# LGT_Mini_Box.net
KiCad netlist of a schematic drawn in Altium Designer
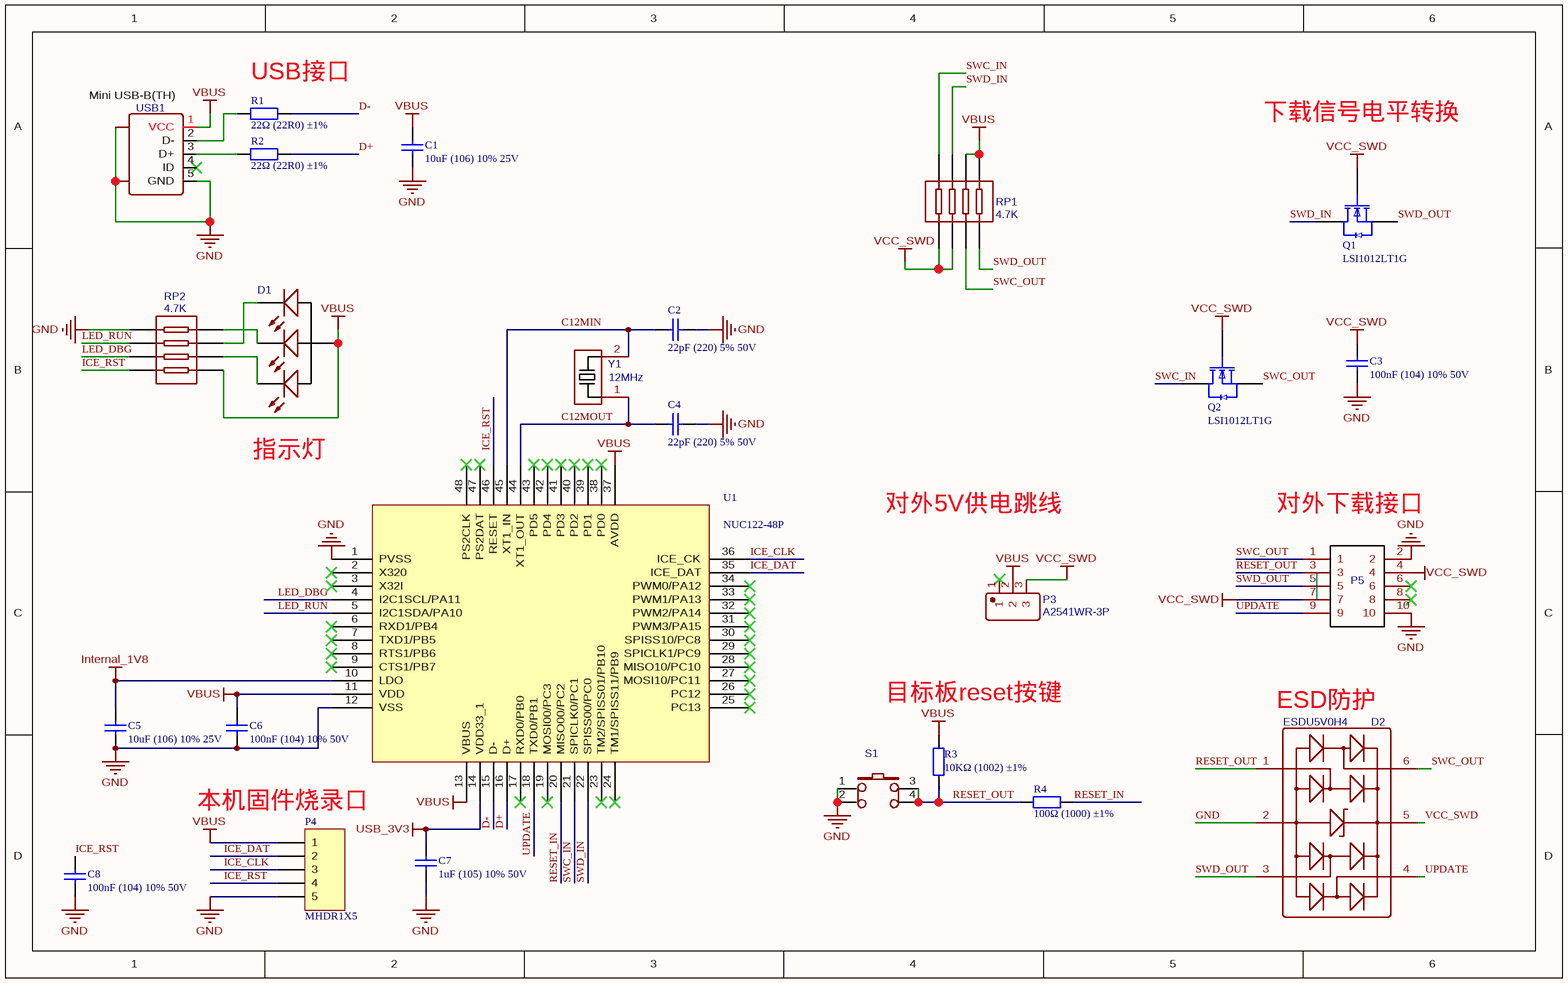
[diagram p0: LGT Mini Box.schdoc]

(export (version "E")
  (design (tool "Eeschema 10.0.6"))
  (components
    (comp (ref "C1")
      (value "10uF (106) 10% 25V")
      (libsource (lib "altium-import") (part "root_1_10uF (106) 10% 25V_"))
    )
    (comp (ref "C2")
      (value "22pF (220) 5% 50V")
      (libsource (lib "altium-import") (part "root_0_22pF (220) 5% 50V_"))
    )
    (comp (ref "C3")
      (value "100nF (104) 10% 50V")
      (libsource (lib "altium-import") (part "root_1_100nF (104) 10% 50V_"))
    )
    (comp (ref "C4")
      (value "22pF (220) 5% 50V")
      (libsource (lib "altium-import") (part "root_0_22pF (220) 5% 50V_"))
    )
    (comp (ref "C5")
      (value "10uF (106) 10% 25V")
      (libsource (lib "altium-import") (part "root_1_10uF (106) 10% 25V_"))
    )
    (comp (ref "C6")
      (value "100nF (104) 10% 50V")
      (libsource (lib "altium-import") (part "root_1_100nF (104) 10% 50V_"))
    )
    (comp (ref "C7")
      (value "1uF (105) 10% 50V")
      (libsource (lib "altium-import") (part "root_1_1uF (105) 10% 50V_"))
    )
    (comp (ref "C8")
      (value "100nF (104) 10% 50V")
      (libsource (lib "altium-import") (part "root_1_100nF (104) 10% 50V_"))
    )
    (comp (ref "D1")
      (value "FM-B2020RGBA-HG")
      (fields (field (name "BOM_SUPPLIER PART") "C108793") (field (name "CONTRIBUTOR") "LCSC"))
      (libsource (lib "altium-import") (part "root_2_FM-B2020RGBA-HG_"))
    )
    (comp (ref "D2")
      (value "ESDU5V0H4")
      (fields (field (name "BOM_SUPPLIER PART") "C84837"))
      (libsource (lib "altium-import") (part "root_3_ESDU5V0H4_"))
    )
    (comp (ref "P3")
      (value "A2541WR-3P")
      (fields (field (name "BOM_SUPPLIER PART") "C225489") (field (name "CONTRIBUTOR") "LCSC"))
      (libsource (lib "altium-import") (part "root_2_A2541WR-3P_"))
    )
    (comp (ref "P4")
      (value "MHDR1X5")
      (fields (field (name "PUBLISHER") "Altium Limited"))
      (libsource (lib "altium-import") (part "root_0_MHDR1X5_"))
    )
    (comp (ref "P5")
      (value "LGT-Link-2.54-2X5P")
      (fields
        (field (name "BOM_MANUFACTURER PART") "IDC Box 2.54mm 2X5P")
        (field (name "BOM_SUPPLIER PART") "C5665")
      )
      (libsource (lib "altium-import") (part "root_0_LGT-Link-2.54-2X5P_"))
    )
    (comp (ref "Q1") (value "LSI1012LT1G") (libsource (lib "altium-import") (part "root_3_LSI1012LT1G_")))
    (comp (ref "Q2") (value "LSI1012LT1G") (libsource (lib "altium-import") (part "root_3_LSI1012LT1G_")))
    (comp (ref "R1")
      (value "22Ω (22R0) ±1%")
      (libsource (lib "altium-import") (part "root_0_22Ω (22R0) ±1%_"))
    )
    (comp (ref "R2")
      (value "22Ω (22R0) ±1%")
      (libsource (lib "altium-import") (part "root_0_22Ω (22R0) ±1%_"))
    )
    (comp (ref "R3")
      (value "10KΩ (1002) ±1%")
      (libsource (lib "altium-import") (part "root_1_10KΩ (1002) ±1%_"))
    )
    (comp (ref "R4")
      (value "100Ω (1000) ±1%")
      (libsource (lib "altium-import") (part "root_2_100Ω (1000) ±1%_"))
    )
    (comp (ref "RP1")
      (value "4.7K")
      (fields
        (field (name "BOM_MANUFACTURER PART") "4D03WGJ0472T5E")
        (field (name "BOM_SUPPLIER PART") "C1980")
      )
      (libsource (lib "altium-import") (part "root_1_4.7K_"))
    )
    (comp (ref "RP2")
      (value "4.7K")
      (fields
        (field (name "BOM_MANUFACTURER PART") "4D03WGJ0472T5E")
        (field (name "BOM_SUPPLIER PART") "C1980")
      )
      (libsource (lib "altium-import") (part "root_0_4.7K_"))
    )
    (comp (ref "S1")
      (value "K2-1109DP-I4SW-01")
      (fields (field (name "BOM_SUPPLIER PART") "C223802") (field (name "CONTRIBUTOR") "LCSC"))
      (libsource (lib "altium-import") (part "root_0_K2-1109DP-I4SW-01_"))
    )
    (comp (ref "U1") (value "NUC122-48P") (libsource (lib "altium-import") (part "root_0_NUC122-48P_")))
    (comp (ref "USB1")
      (value "Mini USB-B 5P-Female-TH_C46398")
      (fields
        (field (name "BOM_MANUFACTURER PART") "MINI 5PFemale90Degree plate four feet copper shell LCPVinyl")
        (field (name "BOM_SUPPLIER PART") "C46398")
      )
      (libsource (lib "altium-import") (part "root_0_Mini USB-B 5P-Female-TH_C46398_"))
    )
    (comp (ref "Y1")
      (value "12MHz")
      (fields
        (field (name "BOM_MANUFACTURER PART") "CSTCE16M0V53C-R0")
        (field (name "BOM_SUPPLIER PART") "C91584")
        (field (name "CONTRIBUTOR") "costar")
      )
      (libsource (lib "altium-import") (part "root_1_12MHz_"))
    )
  )
  (nets
    (net (code "1") (name "/C12MIN") (class "Default")
      (node (ref "C2") (pin "1") (pinfunction "1_1") (pintype "passive"))
      (node (ref "U1") (pin "45") (pinfunction "XT1_IN_45") (pintype "passive"))
      (node (ref "Y1") (pin "2") (pinfunction "2_2") (pintype "passive"))
    )
    (net (code "2") (name "/C12MOUT") (class "Default")
      (node (ref "C4") (pin "1") (pinfunction "1_1") (pintype "passive"))
      (node (ref "U1") (pin "44") (pinfunction "XT1_OUT_44") (pintype "passive"))
      (node (ref "Y1") (pin "1") (pinfunction "1_1") (pintype "passive"))
    )
    (net (code "3") (name "/D+") (class "Default")
      (node (ref "R2") (pin "2") (pinfunction "2_2") (pintype "passive"))
      (node (ref "U1") (pin "16") (pinfunction "D+_16") (pintype "passive"))
    )
    (net (code "4") (name "/D-") (class "Default")
      (node (ref "R1") (pin "2") (pinfunction "2_2") (pintype "passive"))
      (node (ref "U1") (pin "15") (pinfunction "D-_15") (pintype "passive"))
    )
    (net (code "5") (name "/ICE_CLK") (class "Default")
      (node (ref "P4") (pin "3") (pinfunction "3_3") (pintype "passive"))
      (node (ref "U1") (pin "36") (pinfunction "ICE_CK_36") (pintype "passive"))
    )
    (net (code "6") (name "/ICE_DAT") (class "Default")
      (node (ref "P4") (pin "2") (pinfunction "2_2") (pintype "passive"))
      (node (ref "U1") (pin "35") (pinfunction "ICE_DAT_35") (pintype "passive"))
    )
    (net (code "7") (name "/ICE_RST") (class "Default")
      (node (ref "C8") (pin "2") (pinfunction "2_2") (pintype "passive"))
      (node (ref "P4") (pin "4") (pinfunction "4_4") (pintype "passive"))
      (node (ref "RP2") (pin "4") (pinfunction "4_4") (pintype "passive"))
      (node (ref "U1") (pin "46") (pinfunction "RESET_46") (pintype "passive"))
    )
    (net (code "8") (name "/LED_DBG") (class "Default")
      (node (ref "RP2") (pin "3") (pinfunction "3_3") (pintype "passive"))
      (node (ref "U1") (pin "4") (pinfunction "I2C1SCL/PA11_4") (pintype "passive"))
    )
    (net (code "9") (name "/LED_RUN") (class "Default")
      (node (ref "RP2") (pin "2") (pinfunction "2_2") (pintype "passive"))
      (node (ref "U1") (pin "5") (pinfunction "I2C1SDA/PA10_5") (pintype "passive"))
    )
    (net (code "10") (name "/RESET_IN") (class "Default")
      (node (ref "R4") (pin "1") (pinfunction "1_1") (pintype "passive"))
      (node (ref "U1") (pin "20") (pinfunction "MISO00/PC2_20") (pintype "passive"))
    )
    (net (code "11") (name "/RESET_OUT") (class "Default")
      (node (ref "D2") (pin "1") (pinfunction "IO1_1") (pintype "passive"))
      (node (ref "P5") (pin "3") (pinfunction "3_3") (pintype "passive"))
      (node (ref "R3") (pin "1") (pinfunction "1_1") (pintype "passive"))
      (node (ref "R4") (pin "2") (pinfunction "2_2") (pintype "passive"))
      (node (ref "S1") (pin "3") (pinfunction "3_3") (pintype "passive"))
      (node (ref "S1") (pin "4") (pinfunction "4_4") (pintype "passive"))
    )
    (net (code "12") (name "/SWC_IN") (class "Default")
      (node (ref "Q2") (pin "3") (pinfunction "D_3") (pintype "passive"))
      (node (ref "RP1") (pin "8") (pinfunction "8_8") (pintype "passive"))
      (node (ref "U1") (pin "21") (pinfunction "SPICLK0/PC1_21") (pintype "passive"))
    )
    (net (code "13") (name "/SWC_OUT") (class "Default")
      (node (ref "D2") (pin "6") (pinfunction "IO2_6") (pintype "passive"))
      (node (ref "P5") (pin "1") (pinfunction "1_1") (pintype "passive"))
      (node (ref "Q2") (pin "2") (pinfunction "S_2") (pintype "passive"))
      (node (ref "RP1") (pin "3") (pinfunction "3_3") (pintype "passive"))
    )
    (net (code "14") (name "/SWD_IN") (class "Default")
      (node (ref "Q1") (pin "3") (pinfunction "D_3") (pintype "passive"))
      (node (ref "RP1") (pin "7") (pinfunction "7_7") (pintype "passive"))
      (node (ref "U1") (pin "22") (pinfunction "SPISS00/PC0_22") (pintype "passive"))
    )
    (net (code "15") (name "/SWD_OUT") (class "Default")
      (node (ref "D2") (pin "3") (pinfunction "IO3_3") (pintype "passive"))
      (node (ref "P5") (pin "5") (pinfunction "5_5") (pintype "passive"))
      (node (ref "Q1") (pin "2") (pinfunction "S_2") (pintype "passive"))
      (node (ref "RP1") (pin "4") (pinfunction "4_4") (pintype "passive"))
    )
    (net (code "16") (name "/UPDATE") (class "Default")
      (node (ref "D2") (pin "4") (pinfunction "IO4_4") (pintype "passive"))
      (node (ref "P5") (pin "9") (pinfunction "9_9") (pintype "passive"))
      (node (ref "U1") (pin "18") (pinfunction "TXD0/PB1_18") (pintype "passive"))
    )
    (net (code "17") (name "GND") (class "Default")
      (node (ref "C1") (pin "1") (pinfunction "1_1") (pintype "passive"))
      (node (ref "C2") (pin "2") (pinfunction "2_2") (pintype "passive"))
      (node (ref "C3") (pin "1") (pinfunction "1_1") (pintype "passive"))
      (node (ref "C4") (pin "2") (pinfunction "2_2") (pintype "passive"))
      (node (ref "C5") (pin "1") (pinfunction "1_1") (pintype "passive"))
      (node (ref "C6") (pin "1") (pinfunction "1_1") (pintype "passive"))
      (node (ref "C7") (pin "1") (pinfunction "1_1") (pintype "passive"))
      (node (ref "C8") (pin "1") (pinfunction "1_1") (pintype "passive"))
      (node (ref "D2") (pin "2") (pinfunction "GND_2") (pintype "passive"))
      (node (ref "P4") (pin "5") (pinfunction "5_5") (pintype "passive"))
      (node (ref "P5") (pin "10") (pinfunction "10_10") (pintype "passive"))
      (node (ref "P5") (pin "2") (pinfunction "2_2") (pintype "passive"))
      (node (ref "RP2") (pin "1") (pinfunction "1_1") (pintype "passive"))
      (node (ref "S1") (pin "1") (pinfunction "1_1") (pintype "passive"))
      (node (ref "S1") (pin "2") (pinfunction "2_2") (pintype "passive"))
      (node (ref "U1") (pin "1") (pinfunction "PVSS_1") (pintype "passive"))
      (node (ref "U1") (pin "12") (pinfunction "VSS_12") (pintype "passive"))
      (node (ref "USB1") (pin "0") (pinfunction "0_0") (pintype "passive"))
      (node (ref "USB1") (pin "5") (pinfunction "GND_5") (pintype "passive"))
    )
    (net (code "18") (name "Internal_1V8") (class "Default")
      (node (ref "C5") (pin "2") (pinfunction "2_2") (pintype "passive"))
      (node (ref "U1") (pin "10") (pinfunction "LDO_10") (pintype "passive"))
    )
    (net (code "19") (name "Net-(D1-K-Pad1)") (class "Default")
      (node (ref "D1") (pin "1") (pinfunction "K_1") (pintype "passive"))
      (node (ref "RP2") (pin "6") (pinfunction "6_6") (pintype "passive"))
    )
    (net (code "20") (name "Net-(D1-K-Pad2)") (class "Default")
      (node (ref "D1") (pin "2") (pinfunction "K_2") (pintype "passive"))
      (node (ref "RP2") (pin "8") (pinfunction "8_8") (pintype "passive"))
    )
    (net (code "21") (name "Net-(D1-K-Pad4)") (class "Default")
      (node (ref "D1") (pin "4") (pinfunction "K_4") (pintype "passive"))
      (node (ref "RP2") (pin "7") (pinfunction "7_7") (pintype "passive"))
    )
    (net (code "22") (name "Net-(USB1-D+)") (class "Default")
      (node (ref "R2") (pin "1") (pinfunction "1_1") (pintype "passive"))
      (node (ref "USB1") (pin "3") (pinfunction "D+_3") (pintype "passive"))
    )
    (net (code "23") (name "Net-(USB1-D-)") (class "Default")
      (node (ref "R1") (pin "1") (pinfunction "1_1") (pintype "passive"))
      (node (ref "USB1") (pin "2") (pinfunction "D-_2") (pintype "passive"))
    )
    (net (code "24") (name "USB_3V3") (class "Default")
      (node (ref "C7") (pin "2") (pinfunction "2_2") (pintype "passive"))
      (node (ref "U1") (pin "14") (pinfunction "VDD33_1_14") (pintype "passive"))
    )
    (net (code "25") (name "VBUS") (class "Default")
      (node (ref "C1") (pin "2") (pinfunction "2_2") (pintype "passive"))
      (node (ref "C6") (pin "2") (pinfunction "2_2") (pintype "passive"))
      (node (ref "D1") (pin "3") (pinfunction "A_3") (pintype "passive"))
      (node (ref "P3") (pin "2") (pinfunction "2_2") (pintype "passive"))
      (node (ref "P4") (pin "1") (pinfunction "1_1") (pintype "passive"))
      (node (ref "R3") (pin "2") (pinfunction "2_2") (pintype "passive"))
      (node (ref "RP1") (pin "5") (pinfunction "5_5") (pintype "passive"))
      (node (ref "RP1") (pin "6") (pinfunction "6_6") (pintype "passive"))
      (node (ref "RP2") (pin "5") (pinfunction "5_5") (pintype "passive"))
      (node (ref "U1") (pin "11") (pinfunction "VDD_11") (pintype "passive"))
      (node (ref "U1") (pin "13") (pinfunction "VBUS_13") (pintype "passive"))
      (node (ref "U1") (pin "37") (pinfunction "AVDD_37") (pintype "passive"))
      (node (ref "USB1") (pin "1") (pinfunction "VCC_1") (pintype "passive"))
    )
    (net (code "26") (name "VCC_SWD") (class "Default")
      (node (ref "C3") (pin "2") (pinfunction "2_2") (pintype "passive"))
      (node (ref "D2") (pin "5") (pinfunction "VCC_5") (pintype "passive"))
      (node (ref "P3") (pin "3") (pinfunction "3_3") (pintype "passive"))
      (node (ref "P5") (pin "4") (pinfunction "4_4") (pintype "passive"))
      (node (ref "P5") (pin "7") (pinfunction "7_7") (pintype "passive"))
      (node (ref "Q1") (pin "1") (pinfunction "G_1") (pintype "passive"))
      (node (ref "Q2") (pin "1") (pinfunction "G_1") (pintype "passive"))
      (node (ref "RP1") (pin "1") (pinfunction "1_1") (pintype "passive"))
      (node (ref "RP1") (pin "2") (pinfunction "2_2") (pintype "passive"))
    )
    (net (code "27") (name "unconnected-(P3-Pad1)") (class "Default")
      (node (ref "P3") (pin "1") (pinfunction "1_1") (pintype "passive+no_connect"))
    )
    (net (code "28") (name "unconnected-(P5-Pad6)") (class "Default")
      (node (ref "P5") (pin "6") (pinfunction "6_6") (pintype "passive+no_connect"))
    )
    (net (code "29") (name "unconnected-(P5-Pad8)") (class "Default")
      (node (ref "P5") (pin "8") (pinfunction "8_8") (pintype "passive+no_connect"))
    )
    (net (code "30") (name "unconnected-(U1-CTS1{slash}PB7-Pad9)") (class "Default")
      (node (ref "U1") (pin "9") (pinfunction "CTS1/PB7_9") (pintype "passive+no_connect"))
    )
    (net (code "31") (name "unconnected-(U1-MISO10{slash}PC10-Pad28)") (class "Default")
      (node (ref "U1") (pin "28") (pinfunction "MISO10/PC10_28") (pintype "passive+no_connect"))
    )
    (net (code "32") (name "unconnected-(U1-MOSI00{slash}PC3-Pad19)") (class "Default")
      (node (ref "U1") (pin "19") (pinfunction "MOSI00/PC3_19") (pintype "passive+no_connect"))
    )
    (net (code "33") (name "unconnected-(U1-MOSI10{slash}PC11-Pad27)") (class "Default")
      (node (ref "U1") (pin "27") (pinfunction "MOSI10/PC11_27") (pintype "passive+no_connect"))
    )
    (net (code "34") (name "unconnected-(U1-PC12-Pad26)") (class "Default")
      (node (ref "U1") (pin "26") (pinfunction "PC12_26") (pintype "passive+no_connect"))
    )
    (net (code "35") (name "unconnected-(U1-PC13-Pad25)") (class "Default")
      (node (ref "U1") (pin "25") (pinfunction "PC13_25") (pintype "passive+no_connect"))
    )
    (net (code "36") (name "unconnected-(U1-PD0-Pad38)") (class "Default")
      (node (ref "U1") (pin "38") (pinfunction "PD0_38") (pintype "passive+no_connect"))
    )
    (net (code "37") (name "unconnected-(U1-PD1-Pad39)") (class "Default")
      (node (ref "U1") (pin "39") (pinfunction "PD1_39") (pintype "passive+no_connect"))
    )
    (net (code "38") (name "unconnected-(U1-PD2-Pad40)") (class "Default")
      (node (ref "U1") (pin "40") (pinfunction "PD2_40") (pintype "passive+no_connect"))
    )
    (net (code "39") (name "unconnected-(U1-PD3-Pad41)") (class "Default")
      (node (ref "U1") (pin "41") (pinfunction "PD3_41") (pintype "passive+no_connect"))
    )
    (net (code "40") (name "unconnected-(U1-PD4-Pad42)") (class "Default")
      (node (ref "U1") (pin "42") (pinfunction "PD4_42") (pintype "passive+no_connect"))
    )
    (net (code "41") (name "unconnected-(U1-PD5-Pad43)") (class "Default")
      (node (ref "U1") (pin "43") (pinfunction "PD5_43") (pintype "passive+no_connect"))
    )
    (net (code "42") (name "unconnected-(U1-PS2CLK-Pad48)") (class "Default")
      (node (ref "U1") (pin "48") (pinfunction "PS2CLK_48") (pintype "passive+no_connect"))
    )
    (net (code "43") (name "unconnected-(U1-PS2DAT-Pad47)") (class "Default")
      (node (ref "U1") (pin "47") (pinfunction "PS2DAT_47") (pintype "passive+no_connect"))
    )
    (net (code "44") (name "unconnected-(U1-PWM0{slash}PA12-Pad34)") (class "Default")
      (node (ref "U1") (pin "34") (pinfunction "PWM0/PA12_34") (pintype "passive+no_connect"))
    )
    (net (code "45") (name "unconnected-(U1-PWM1{slash}PA13-Pad33)") (class "Default")
      (node (ref "U1") (pin "33") (pinfunction "PWM1/PA13_33") (pintype "passive+no_connect"))
    )
    (net (code "46") (name "unconnected-(U1-PWM2{slash}PA14-Pad32)") (class "Default")
      (node (ref "U1") (pin "32") (pinfunction "PWM2/PA14_32") (pintype "passive+no_connect"))
    )
    (net (code "47") (name "unconnected-(U1-PWM3{slash}PA15-Pad31)") (class "Default")
      (node (ref "U1") (pin "31") (pinfunction "PWM3/PA15_31") (pintype "passive+no_connect"))
    )
    (net (code "48") (name "unconnected-(U1-RTS1{slash}PB6-Pad8)") (class "Default")
      (node (ref "U1") (pin "8") (pinfunction "RTS1/PB6_8") (pintype "passive+no_connect"))
    )
    (net (code "49") (name "unconnected-(U1-RXD0{slash}PB0-Pad17)") (class "Default")
      (node (ref "U1") (pin "17") (pinfunction "RXD0/PB0_17") (pintype "passive+no_connect"))
    )
    (net (code "50") (name "unconnected-(U1-RXD1{slash}PB4-Pad6)") (class "Default")
      (node (ref "U1") (pin "6") (pinfunction "RXD1/PB4_6") (pintype "passive+no_connect"))
    )
    (net (code "51") (name "unconnected-(U1-SPICLK1{slash}PC9-Pad29)") (class "Default")
      (node (ref "U1") (pin "29") (pinfunction "SPICLK1/PC9_29") (pintype "passive+no_connect"))
    )
    (net (code "52") (name "unconnected-(U1-SPISS10{slash}PC8-Pad30)") (class "Default")
      (node (ref "U1") (pin "30") (pinfunction "SPISS10/PC8_30") (pintype "passive+no_connect"))
    )
    (net (code "53") (name "unconnected-(U1-TM1{slash}SPISS11{slash}PB9-Pad24)") (class "Default")
      (node (ref "U1") (pin "24") (pinfunction "TM1/SPISS11/PB9_24") (pintype "passive+no_connect"))
    )
    (net (code "54") (name "unconnected-(U1-TM2{slash}SPISS01{slash}PB10-Pad23)") (class "Default")
      (node (ref "U1") (pin "23") (pinfunction "TM2/SPISS01/PB10_23") (pintype "passive+no_connect"))
    )
    (net (code "55") (name "unconnected-(U1-TXD1{slash}PB5-Pad7)") (class "Default")
      (node (ref "U1") (pin "7") (pinfunction "TXD1/PB5_7") (pintype "passive+no_connect"))
    )
    (net (code "56") (name "unconnected-(U1-X32I-Pad3)") (class "Default")
      (node (ref "U1") (pin "3") (pinfunction "X32I_3") (pintype "passive+no_connect"))
    )
    (net (code "57") (name "unconnected-(U1-X320-Pad2)") (class "Default")
      (node (ref "U1") (pin "2") (pinfunction "X320_2") (pintype "passive+no_connect"))
    )
    (net (code "58") (name "unconnected-(USB1-ID-Pad4)") (class "Default")
      (node (ref "USB1") (pin "4") (pinfunction "ID_4") (pintype "passive+no_connect"))
    )
  )
)
